# I2CInterface.net
KiCad netlist of a schematic drawn in Altium Designer
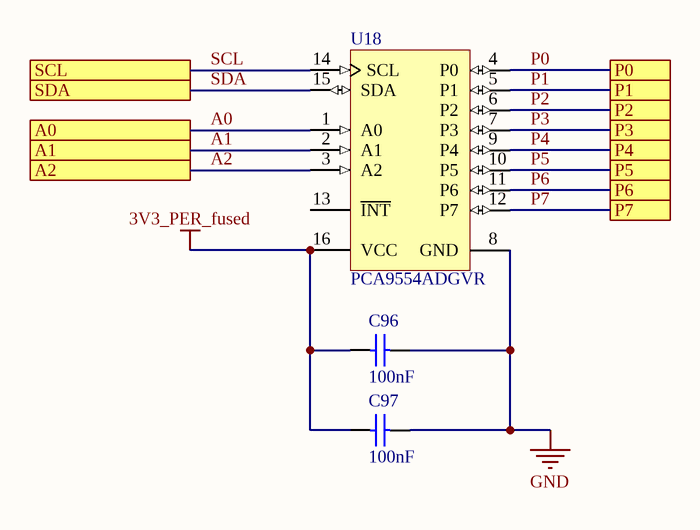
[diagram p0: I2CInterface.SchDoc]

(export (version "E")
  (design (tool "Eeschema 10.0.6"))
  (components
    (comp (ref "C96")
      (value "100nF")
      (footprint "CAPC1608X07N")
      (fields (field (name "MF") "Würth") (field (name "MPN") "885012206071") (field (name "VOLTAGE") "25V"))
      (libsource (lib "UltraZohm_ADC") (part "Cap_0603"))
    )
    (comp (ref "C97")
      (value "100nF")
      (footprint "CAPC1608X07N")
      (fields (field (name "MF") "Würth") (field (name "MPN") "885012206071") (field (name "VOLTAGE") "25V"))
      (libsource (lib "UltraZohm_ADC") (part "Cap_0603"))
    )
    (comp (ref "U18")
      (value "PCA9554ADGVR")
      (footprint "DGV0016A_L")
      (fields (field (name "MANUFACTURER") "Texas Instruments"))
      (libsource (lib "Altium Content Vault") (part "TI-PCA9554A-TVSOP_DGV-16"))
    )
  )
  (nets
    (net (code "1") (name "/A0") (class "Default")
      (node (ref "U18") (pin "1") (pinfunction "A0_1") (pintype "input"))
    )
    (net (code "2") (name "/A1") (class "Default")
      (node (ref "U18") (pin "2") (pinfunction "A1_2") (pintype "input"))
    )
    (net (code "3") (name "/A2") (class "Default")
      (node (ref "U18") (pin "3") (pinfunction "A2_3") (pintype "input"))
    )
    (net (code "4") (name "/P0") (class "Default")
      (node (ref "U18") (pin "4") (pinfunction "P0_4") (pintype "bidirectional"))
    )
    (net (code "5") (name "/P1") (class "Default")
      (node (ref "U18") (pin "5") (pinfunction "P1_5") (pintype "bidirectional"))
    )
    (net (code "6") (name "/P2") (class "Default")
      (node (ref "U18") (pin "6") (pinfunction "P2_6") (pintype "bidirectional"))
    )
    (net (code "7") (name "/P3") (class "Default")
      (node (ref "U18") (pin "7") (pinfunction "P3_7") (pintype "bidirectional"))
    )
    (net (code "8") (name "/P4") (class "Default")
      (node (ref "U18") (pin "9") (pinfunction "P4_9") (pintype "bidirectional"))
    )
    (net (code "9") (name "/P5") (class "Default")
      (node (ref "U18") (pin "10") (pinfunction "P5_10") (pintype "bidirectional"))
    )
    (net (code "10") (name "/P6") (class "Default")
      (node (ref "U18") (pin "11") (pinfunction "P6_11") (pintype "bidirectional"))
    )
    (net (code "11") (name "/P7") (class "Default")
      (node (ref "U18") (pin "12") (pinfunction "P7_12") (pintype "bidirectional"))
    )
    (net (code "12") (name "/SCL") (class "Default")
      (node (ref "U18") (pin "14") (pinfunction "SCL_14") (pintype "input"))
    )
    (net (code "13") (name "/SDA") (class "Default")
      (node (ref "U18") (pin "15") (pinfunction "SDA_15") (pintype "bidirectional"))
    )
    (net (code "14") (name "3V3_PER_fused") (class "Default")
      (node (ref "C96") (pin "1") (pinfunction "1_1") (pintype "passive"))
      (node (ref "C97") (pin "1") (pinfunction "1_1") (pintype "passive"))
      (node (ref "U18") (pin "16") (pinfunction "VCC_16") (pintype "power_in"))
    )
    (net (code "15") (name "GND") (class "Default")
      (node (ref "C96") (pin "2") (pinfunction "2_2") (pintype "passive"))
      (node (ref "C97") (pin "2") (pinfunction "2_2") (pintype "passive"))
      (node (ref "U18") (pin "8") (pinfunction "GND_8") (pintype "power_in"))
    )
    (net (code "16") (name "unconnected-(U18-~{INT}-Pad13)") (class "Default")
      (node (ref "U18") (pin "13") (pinfunction "~{INT}_13") (pintype "open_collector"))
    )
  )
)
